# 07_MIPI_CSI.net
KiCad netlist of a schematic drawn in Altium Designer
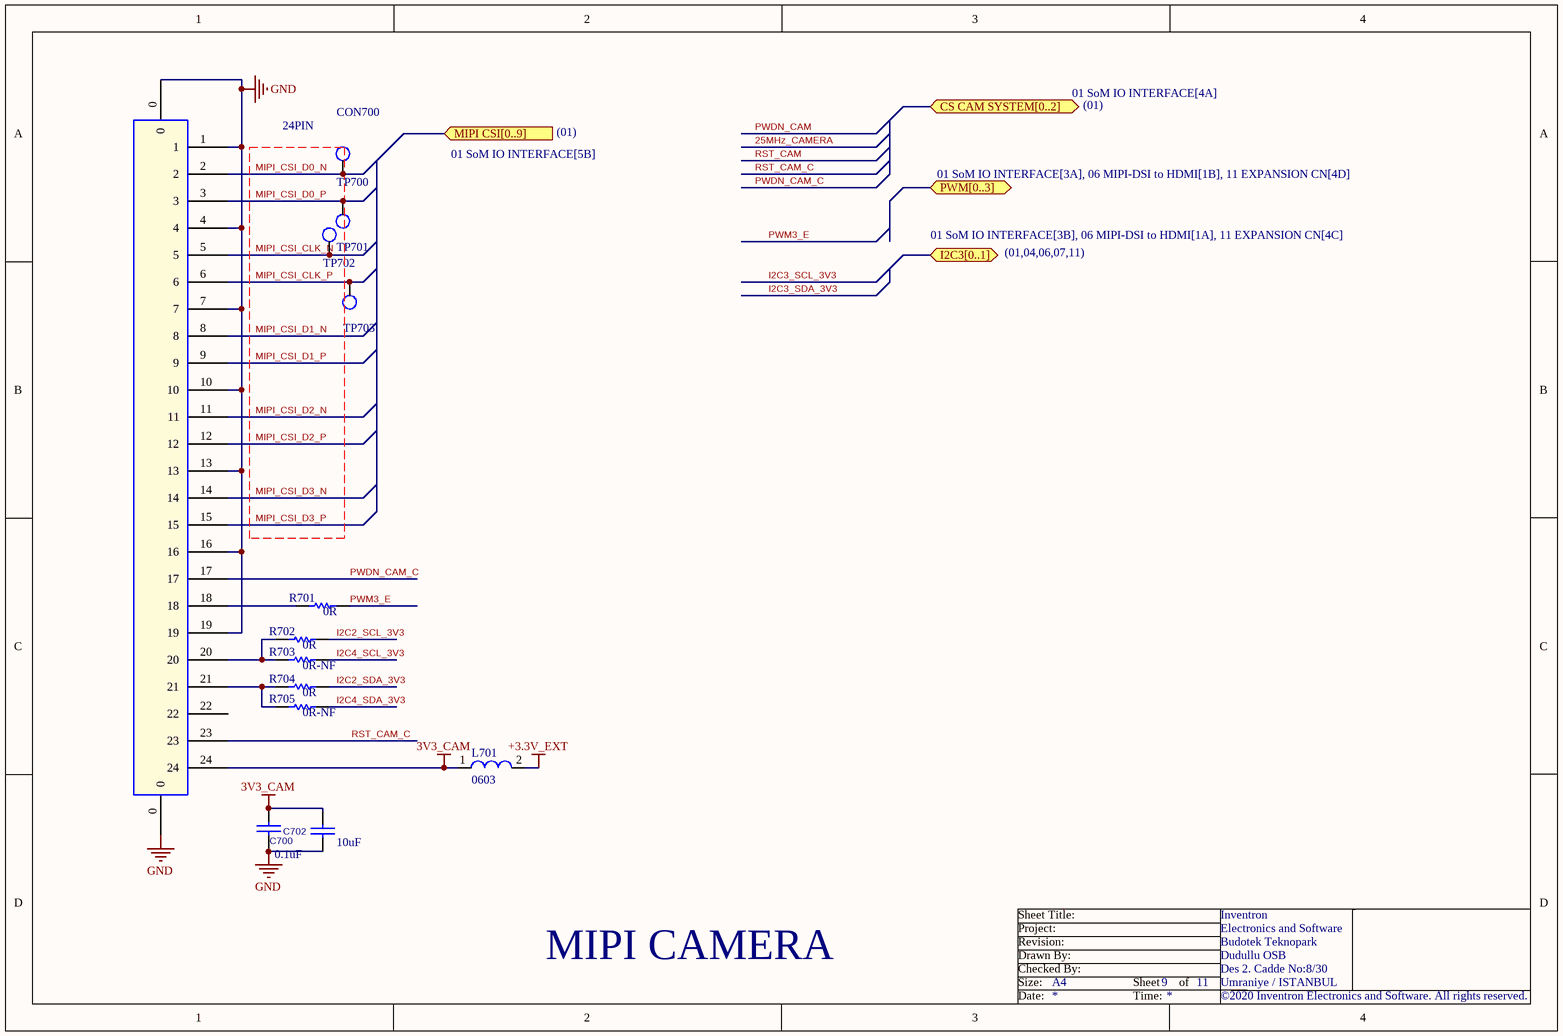
[diagram p0: 07 MIPI CSI.SchDoc]

(export (version "E")
  (design (tool "Eeschema 10.0.6"))
  (components
    (comp (ref "C700")
      (value "0.1uF")
      (footprint "0402_CC")
      (description "CAP VER 0.1UF 16V X7R 0402")
      (fields (field (name "CREATED BY") "LA") (field (name "CHECKED BY") "*"))
      (libsource (lib "ARETE_SCH") (part "CAP-CL05B104KO5NNNC"))
    )
    (comp (ref "C702")
      (value "10uF")
      (footprint "0603_CC")
      (description "CAP CER 10UF 6.3V X6S 0603")
      (fields (field (name "CREATED BY") "LA") (field (name "CHECKED BY") "*"))
      (libsource (lib "ARETE_SCH") (part "CAP-JMK107BC6106MA-T"))
    )
    (comp (ref "CON700")
      (value "24PIN")
      (footprint "24-PIN FPC")
      (description "CONN FPC TOP 24POS 0.50MM R/A")
      (fields (field (name "CREATED BY") "LA") (field (name "CHECKED BY") "*"))
      (libsource (lib "ARETE_SCH") (part "CON-SFV24R-4STBE1HLF(GENIS)"))
    )
    (comp (ref "L701")
      (value "0603")
      (footprint "0603_RES")
      (description "0OHM 0603")
      (fields (field (name "CREATED BY") "EE") (field (name "CHECKED BY") "*"))
      (libsource (lib "ARETE_SCH") (part "IND-FERRITE (RES 0 OHM) 0603"))
    )
    (comp (ref "R701")
      (value "0R")
      (footprint "0402_RES")
      (description "RES 0 OHM JUMPER 1/16W 0402")
      (fields (field (name "CREATED BY") "LA") (field (name "CHECKED BY") "*"))
      (libsource (lib "ARETE_SCH") (part "RES-RMCF0402ZT0R00"))
    )
    (comp (ref "R702")
      (value "0R")
      (footprint "0402_RES")
      (description "RES 0 OHM JUMPER 1/16W 0402")
      (fields (field (name "CREATED BY") "LA") (field (name "CHECKED BY") "*"))
      (libsource (lib "ARETE_SCH") (part "RES-RMCF0402ZT0R00"))
    )
    (comp (ref "R703")
      (value "0R-NF")
      (footprint "0402_RES")
      (description "RES 0 OHM JUMPER 1/16W 0402")
      (fields (field (name "CREATED BY") "LA") (field (name "CHECKED BY") "*"))
      (libsource (lib "ARETE_SCH") (part "RES-RMCF0402ZT0R00"))
    )
    (comp (ref "R704")
      (value "0R")
      (footprint "0402_RES")
      (description "RES 0 OHM JUMPER 1/16W 0402")
      (fields (field (name "CREATED BY") "LA") (field (name "CHECKED BY") "*"))
      (libsource (lib "ARETE_SCH") (part "RES-RMCF0402ZT0R00"))
    )
    (comp (ref "R705")
      (value "0R-NF")
      (footprint "0402_RES")
      (description "RES 0 OHM JUMPER 1/16W 0402")
      (fields (field (name "CREATED BY") "LA") (field (name "CHECKED BY") "*"))
      (libsource (lib "ARETE_SCH") (part "RES-RMCF0402ZT0R00"))
    )
    (comp (ref "TP700")
      (value "TEST POINT 15")
      (footprint "testpoint_15")
      (libsource (lib "X98_CARRIER_V1R2") (part "TEST POINT 15"))
    )
    (comp (ref "TP701")
      (value "TEST POINT 15")
      (footprint "testpoint_15")
      (libsource (lib "X98_CARRIER_V1R2") (part "TEST POINT 15"))
    )
    (comp (ref "TP702")
      (value "TEST POINT 15")
      (footprint "testpoint_15")
      (libsource (lib "X98_CARRIER_V1R2") (part "TEST POINT 15"))
    )
    (comp (ref "TP703")
      (value "TEST POINT 15")
      (footprint "testpoint_15")
      (libsource (lib "X98_CARRIER_V1R2") (part "TEST POINT 15"))
    )
  )
  (nets
    (net (code "7") (name "+3.3V_EXT") (class "Default")
      (node (ref "L701") (pin "2") (pinfunction "2_2") (pintype "passive"))
    )
    (net (code "10") (name "/I2C2_SCL_3V3") (class "Default")
      (node (ref "R702") (pin "2") (pinfunction "2_2") (pintype "passive"))
    )
    (net (code "11") (name "/I2C2_SDA_3V3") (class "Default")
      (node (ref "R704") (pin "2") (pinfunction "2_2") (pintype "passive"))
    )
    (net (code "15") (name "/I2C4_SCL_3V3") (class "Default")
      (node (ref "R703") (pin "2") (pinfunction "2_2") (pintype "passive"))
    )
    (net (code "16") (name "/I2C4_SDA_3V3") (class "Default")
      (node (ref "R705") (pin "2") (pinfunction "2_2") (pintype "passive"))
    )
    (net (code "18") (name "/MIPI_CSI_CLK_N") (class "Default")
      (node (ref "CON700") (pin "5") (pinfunction "5_5") (pintype "passive"))
      (node (ref "TP702") (pin "1") (pinfunction "1_1") (pintype "passive"))
    )
    (net (code "19") (name "/MIPI_CSI_CLK_P") (class "Default")
      (node (ref "CON700") (pin "6") (pinfunction "6_6") (pintype "passive"))
      (node (ref "TP703") (pin "1") (pinfunction "1_1") (pintype "passive"))
    )
    (net (code "20") (name "/MIPI_CSI_D0_N") (class "Default")
      (node (ref "CON700") (pin "2") (pinfunction "2_2") (pintype "passive"))
      (node (ref "TP700") (pin "1") (pinfunction "1_1") (pintype "passive"))
    )
    (net (code "21") (name "/MIPI_CSI_D0_P") (class "Default")
      (node (ref "CON700") (pin "3") (pinfunction "3_3") (pintype "passive"))
      (node (ref "TP701") (pin "1") (pinfunction "1_1") (pintype "passive"))
    )
    (net (code "22") (name "/MIPI_CSI_D1_N") (class "Default")
      (node (ref "CON700") (pin "8") (pinfunction "8_8") (pintype "passive"))
    )
    (net (code "23") (name "/MIPI_CSI_D1_P") (class "Default")
      (node (ref "CON700") (pin "9") (pinfunction "9_9") (pintype "passive"))
    )
    (net (code "24") (name "/MIPI_CSI_D2_N") (class "Default")
      (node (ref "CON700") (pin "11") (pinfunction "11_11") (pintype "passive"))
    )
    (net (code "25") (name "/MIPI_CSI_D2_P") (class "Default")
      (node (ref "CON700") (pin "12") (pinfunction "12_12") (pintype "passive"))
    )
    (net (code "26") (name "/MIPI_CSI_D3_N") (class "Default")
      (node (ref "CON700") (pin "14") (pinfunction "14_14") (pintype "passive"))
    )
    (net (code "27") (name "/MIPI_CSI_D3_P") (class "Default")
      (node (ref "CON700") (pin "15") (pinfunction "15_15") (pintype "passive"))
    )
    (net (code "29") (name "/PWDN_CAM_C") (class "Default")
      (node (ref "CON700") (pin "17") (pinfunction "17_17") (pintype "passive"))
    )
    (net (code "30") (name "/PWM3_E") (class "Default")
      (node (ref "R701") (pin "2") (pinfunction "2_2") (pintype "passive"))
    )
    (net (code "33") (name "/RST_CAM_C") (class "Default")
      (node (ref "CON700") (pin "23") (pinfunction "23_23") (pintype "passive"))
    )
    (net (code "34") (name "3V3_CAM") (class "Default")
      (node (ref "C700") (pin "1") (pinfunction "1_1") (pintype "passive"))
      (node (ref "C702") (pin "1") (pinfunction "1_1") (pintype "passive"))
      (node (ref "CON700") (pin "24") (pinfunction "24_24") (pintype "passive"))
      (node (ref "L701") (pin "1") (pinfunction "1_1") (pintype "passive"))
    )
    (net (code "35") (name "GND") (class "Default")
      (node (ref "C700") (pin "2") (pinfunction "2_2") (pintype "passive"))
      (node (ref "C702") (pin "2") (pinfunction "2_2") (pintype "passive"))
      (node (ref "CON700") (pin "0") (pinfunction "0_0") (pintype "passive"))
      (node (ref "CON700") (pin "1") (pinfunction "1_1") (pintype "passive"))
      (node (ref "CON700") (pin "10") (pinfunction "10_10") (pintype "passive"))
      (node (ref "CON700") (pin "13") (pinfunction "13_13") (pintype "passive"))
      (node (ref "CON700") (pin "16") (pinfunction "16_16") (pintype "passive"))
      (node (ref "CON700") (pin "19") (pinfunction "19_19") (pintype "passive"))
      (node (ref "CON700") (pin "4") (pinfunction "4_4") (pintype "passive"))
      (node (ref "CON700") (pin "7") (pinfunction "7_7") (pintype "passive"))
    )
    (net (code "36") (name "Net-(CON700-Pad18)") (class "Default")
      (node (ref "CON700") (pin "18") (pinfunction "18_18") (pintype "passive"))
      (node (ref "R701") (pin "1") (pinfunction "1_1") (pintype "passive"))
    )
    (net (code "37") (name "Net-(CON700-Pad20)") (class "Default")
      (node (ref "CON700") (pin "20") (pinfunction "20_20") (pintype "passive"))
      (node (ref "R702") (pin "1") (pinfunction "1_1") (pintype "passive"))
      (node (ref "R703") (pin "1") (pinfunction "1_1") (pintype "passive"))
    )
    (net (code "38") (name "Net-(CON700-Pad21)") (class "Default")
      (node (ref "CON700") (pin "21") (pinfunction "21_21") (pintype "passive"))
      (node (ref "R704") (pin "1") (pinfunction "1_1") (pintype "passive"))
      (node (ref "R705") (pin "1") (pinfunction "1_1") (pintype "passive"))
    )
    (net (code "39") (name "unconnected-(CON700-Pad22)") (class "Default")
      (node (ref "CON700") (pin "22") (pinfunction "22_22") (pintype "passive"))
    )
  )
)
